# myirBoard.net
KiCad netlist of a schematic drawn in Altium Designer
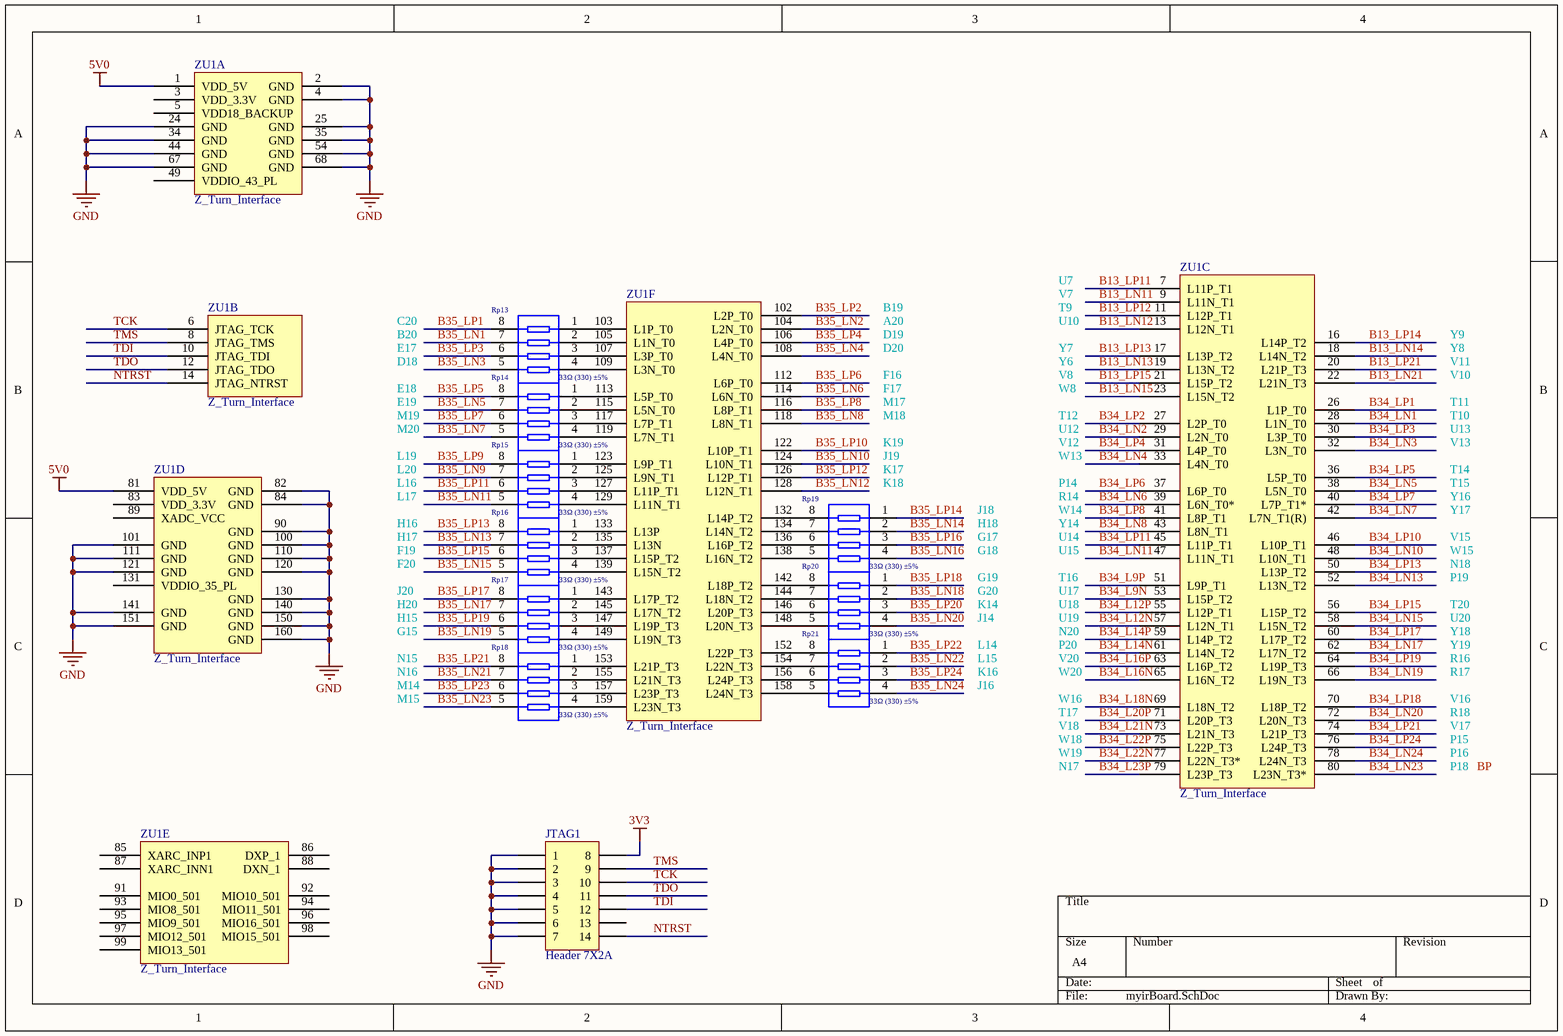
[diagram p0: myirBoard.SchDoc]

(export (version "E")
  (design (tool "Eeschema 10.0.6"))
  (components
    (comp (ref "JTAG1")
      (value "Header 7X2A")
      (footprint "HDR2X7_CEN")
      (description "Header, 7-Pin, Dual row")
      (fields (field (name "PUBLISHER") "Altium Limited"))
      (libsource (lib "Miscellaneous Connectors") (part "Header 7X2A"))
    )
    (comp (ref "Rp13")
      (value "33Ω (330) ±5%")
      (footprint "0402_Rx4")
      (description "贴片排阻")
      (libsource (lib "Miscellaneous Devices LC") (part "0402*4 33Ω (330) 5%"))
    )
    (comp (ref "Rp14")
      (value "33Ω (330) ±5%")
      (footprint "0402_Rx4")
      (description "贴片排阻")
      (libsource (lib "Miscellaneous Devices LC") (part "0402*4 33Ω (330) 5%"))
    )
    (comp (ref "Rp15")
      (value "33Ω (330) ±5%")
      (footprint "0402_Rx4")
      (description "贴片排阻")
      (libsource (lib "Miscellaneous Devices LC") (part "0402*4 33Ω (330) 5%"))
    )
    (comp (ref "Rp16")
      (value "33Ω (330) ±5%")
      (footprint "0402_Rx4")
      (description "贴片排阻")
      (libsource (lib "Miscellaneous Devices LC") (part "0402*4 33Ω (330) 5%"))
    )
    (comp (ref "Rp17")
      (value "33Ω (330) ±5%")
      (footprint "0402_Rx4")
      (description "贴片排阻")
      (libsource (lib "Miscellaneous Devices LC") (part "0402*4 33Ω (330) 5%"))
    )
    (comp (ref "Rp18")
      (value "33Ω (330) ±5%")
      (footprint "0402_Rx4")
      (description "贴片排阻")
      (libsource (lib "Miscellaneous Devices LC") (part "0402*4 33Ω (330) 5%"))
    )
    (comp (ref "Rp19")
      (value "33Ω (330) ±5%")
      (footprint "0402_Rx4")
      (description "贴片排阻")
      (libsource (lib "Miscellaneous Devices LC") (part "0402*4 33Ω (330) 5%"))
    )
    (comp (ref "Rp20")
      (value "33Ω (330) ±5%")
      (footprint "0402_Rx4")
      (description "贴片排阻")
      (libsource (lib "Miscellaneous Devices LC") (part "0402*4 33Ω (330) 5%"))
    )
    (comp (ref "Rp21")
      (value "33Ω (330) ±5%")
      (footprint "0402_Rx4")
      (description "贴片排阻")
      (libsource (lib "Miscellaneous Devices LC") (part "0402*4 33Ω (330) 5%"))
    )
    (comp (ref "ZU1")
      (value "Z_Turn_Interface")
      (footprint "ZTURN")
      (libsource (lib "zynqEXP_Schlib") (part "Z_Turn_Interface"))
    )
  )
  (nets
    (net (code "2") (name "/B13_LN11") (class "Default")
      (node (ref "ZU1") (pin "9") (pinfunction "L11N_T1_9") (pintype "passive"))
    )
    (net (code "3") (name "/B13_LN12") (class "Default")
      (node (ref "ZU1") (pin "13") (pinfunction "L12N_T1_13") (pintype "passive"))
    )
    (net (code "4") (name "/B13_LN13") (class "Default")
      (node (ref "ZU1") (pin "19") (pinfunction "L13N_T2_19") (pintype "passive"))
    )
    (net (code "5") (name "/B13_LN14") (class "Default")
      (node (ref "ZU1") (pin "18") (pinfunction "L14N_T2_18") (pintype "passive"))
    )
    (net (code "6") (name "/B13_LN15") (class "Default")
      (node (ref "ZU1") (pin "23") (pinfunction "L15N_T2_23") (pintype "passive"))
    )
    (net (code "7") (name "/B13_LN21") (class "Default")
      (node (ref "ZU1") (pin "22") (pinfunction "L21N_T3_22") (pintype "passive"))
    )
    (net (code "8") (name "/B13_LP11") (class "Default")
      (node (ref "ZU1") (pin "7") (pinfunction "L11P_T1_7") (pintype "passive"))
    )
    (net (code "9") (name "/B13_LP12") (class "Default")
      (node (ref "ZU1") (pin "11") (pinfunction "L12P_T1_11") (pintype "passive"))
    )
    (net (code "10") (name "/B13_LP13") (class "Default")
      (node (ref "ZU1") (pin "17") (pinfunction "L13P_T2_17") (pintype "passive"))
    )
    (net (code "11") (name "/B13_LP14") (class "Default")
      (node (ref "ZU1") (pin "16") (pinfunction "L14P_T2_16") (pintype "passive"))
    )
    (net (code "12") (name "/B13_LP15") (class "Default")
      (node (ref "ZU1") (pin "21") (pinfunction "L15P_T2_21") (pintype "passive"))
    )
    (net (code "13") (name "/B13_LP21") (class "Default")
      (node (ref "ZU1") (pin "20") (pinfunction "L21P_T3_20") (pintype "passive"))
    )
    (net (code "16") (name "/B34_L9N") (class "Default")
      (node (ref "ZU1") (pin "53") (pinfunction "L15P_T2_53") (pintype "passive"))
    )
    (net (code "17") (name "/B34_L9P") (class "Default")
      (node (ref "ZU1") (pin "51") (pinfunction "L9P_T1_51") (pintype "passive"))
    )
    (net (code "18") (name "/B34_L12N") (class "Default")
      (node (ref "ZU1") (pin "57") (pinfunction "L12N_T1_57") (pintype "passive"))
    )
    (net (code "19") (name "/B34_L12P") (class "Default")
      (node (ref "ZU1") (pin "55") (pinfunction "L12P_T1_55") (pintype "passive"))
    )
    (net (code "20") (name "/B34_L14N") (class "Default")
      (node (ref "ZU1") (pin "61") (pinfunction "L14N_T2_61") (pintype "passive"))
    )
    (net (code "21") (name "/B34_L14P") (class "Default")
      (node (ref "ZU1") (pin "59") (pinfunction "L14P_T2_59") (pintype "passive"))
    )
    (net (code "22") (name "/B34_L16N") (class "Default")
      (node (ref "ZU1") (pin "65") (pinfunction "L16N_T2_65") (pintype "passive"))
    )
    (net (code "23") (name "/B34_L16P") (class "Default")
      (node (ref "ZU1") (pin "63") (pinfunction "L16P_T2_63") (pintype "passive"))
    )
    (net (code "24") (name "/B34_L18N") (class "Default")
      (node (ref "ZU1") (pin "69") (pinfunction "L18N_T2_69") (pintype "passive"))
    )
    (net (code "25") (name "/B34_L20P") (class "Default")
      (node (ref "ZU1") (pin "71") (pinfunction "L20P_T3_71") (pintype "passive"))
    )
    (net (code "26") (name "/B34_L21N") (class "Default")
      (node (ref "ZU1") (pin "73") (pinfunction "L21N_T3_73") (pintype "passive"))
    )
    (net (code "27") (name "/B34_L22N") (class "Default")
      (node (ref "ZU1") (pin "77") (pinfunction "L22N_T3*_77") (pintype "passive"))
    )
    (net (code "28") (name "/B34_L22P") (class "Default")
      (node (ref "ZU1") (pin "75") (pinfunction "L22P_T3_75") (pintype "passive"))
    )
    (net (code "29") (name "/B34_L23P") (class "Default")
      (node (ref "ZU1") (pin "79") (pinfunction "L23P_T3_79") (pintype "passive"))
    )
    (net (code "30") (name "/B34_LN1") (class "Default")
      (node (ref "ZU1") (pin "28") (pinfunction "L1N_T0_28") (pintype "passive"))
    )
    (net (code "31") (name "/B34_LN2") (class "Default")
      (node (ref "ZU1") (pin "29") (pinfunction "L2N_T0_29") (pintype "passive"))
    )
    (net (code "32") (name "/B34_LN3") (class "Default")
      (node (ref "ZU1") (pin "32") (pinfunction "L3N_T0_32") (pintype "passive"))
    )
    (net (code "33") (name "/B34_LN4") (class "Default")
      (node (ref "ZU1") (pin "33") (pinfunction "L4N_T0_33") (pintype "passive"))
    )
    (net (code "34") (name "/B34_LN5") (class "Default")
      (node (ref "ZU1") (pin "38") (pinfunction "L5N_T0_38") (pintype "passive"))
    )
    (net (code "35") (name "/B34_LN6") (class "Default")
      (node (ref "ZU1") (pin "39") (pinfunction "L6N_T0*_39") (pintype "passive"))
    )
    (net (code "36") (name "/B34_LN7") (class "Default")
      (node (ref "ZU1") (pin "42") (pinfunction "L7N_T1(R)_42") (pintype "passive"))
    )
    (net (code "37") (name "/B34_LN8") (class "Default")
      (node (ref "ZU1") (pin "43") (pinfunction "L8N_T1_43") (pintype "passive"))
    )
    (net (code "38") (name "/B34_LN10") (class "Default")
      (node (ref "ZU1") (pin "48") (pinfunction "L10N_T1_48") (pintype "passive"))
    )
    (net (code "39") (name "/B34_LN11") (class "Default")
      (node (ref "ZU1") (pin "47") (pinfunction "L11N_T1_47") (pintype "passive"))
    )
    (net (code "40") (name "/B34_LN13") (class "Default")
      (node (ref "ZU1") (pin "52") (pinfunction "L13N_T2_52") (pintype "passive"))
    )
    (net (code "41") (name "/B34_LN15") (class "Default")
      (node (ref "ZU1") (pin "58") (pinfunction "L15N_T2_58") (pintype "passive"))
    )
    (net (code "42") (name "/B34_LN17") (class "Default")
      (node (ref "ZU1") (pin "62") (pinfunction "L17N_T2_62") (pintype "passive"))
    )
    (net (code "43") (name "/B34_LN19") (class "Default")
      (node (ref "ZU1") (pin "66") (pinfunction "L19N_T3_66") (pintype "passive"))
    )
    (net (code "44") (name "/B34_LN20") (class "Default")
      (node (ref "ZU1") (pin "72") (pinfunction "L20N_T3_72") (pintype "passive"))
    )
    (net (code "45") (name "/B34_LN23") (class "Default")
      (node (ref "ZU1") (pin "80") (pinfunction "L23N_T3*_80") (pintype "passive"))
    )
    (net (code "46") (name "/B34_LN24") (class "Default")
      (node (ref "ZU1") (pin "78") (pinfunction "L24N_T3_78") (pintype "passive"))
    )
    (net (code "47") (name "/B34_LP1") (class "Default")
      (node (ref "ZU1") (pin "26") (pinfunction "L1P_T0_26") (pintype "passive"))
    )
    (net (code "48") (name "/B34_LP2") (class "Default")
      (node (ref "ZU1") (pin "27") (pinfunction "L2P_T0_27") (pintype "passive"))
    )
    (net (code "49") (name "/B34_LP3") (class "Default")
      (node (ref "ZU1") (pin "30") (pinfunction "L3P_T0_30") (pintype "passive"))
    )
    (net (code "50") (name "/B34_LP4") (class "Default")
      (node (ref "ZU1") (pin "31") (pinfunction "L4P_T0_31") (pintype "passive"))
    )
    (net (code "51") (name "/B34_LP5") (class "Default")
      (node (ref "ZU1") (pin "36") (pinfunction "L5P_T0_36") (pintype "passive"))
    )
    (net (code "52") (name "/B34_LP6") (class "Default")
      (node (ref "ZU1") (pin "37") (pinfunction "L6P_T0_37") (pintype "passive"))
    )
    (net (code "53") (name "/B34_LP7") (class "Default")
      (node (ref "ZU1") (pin "40") (pinfunction "L7P_T1*_40") (pintype "passive"))
    )
    (net (code "54") (name "/B34_LP8") (class "Default")
      (node (ref "ZU1") (pin "41") (pinfunction "L8P_T1_41") (pintype "passive"))
    )
    (net (code "55") (name "/B34_LP10") (class "Default")
      (node (ref "ZU1") (pin "46") (pinfunction "L10P_T1_46") (pintype "passive"))
    )
    (net (code "56") (name "/B34_LP11") (class "Default")
      (node (ref "ZU1") (pin "45") (pinfunction "L11P_T1_45") (pintype "passive"))
    )
    (net (code "57") (name "/B34_LP13") (class "Default")
      (node (ref "ZU1") (pin "50") (pinfunction "L13P_T2_50") (pintype "passive"))
    )
    (net (code "58") (name "/B34_LP15") (class "Default")
      (node (ref "ZU1") (pin "56") (pinfunction "L15P_T2_56") (pintype "passive"))
    )
    (net (code "59") (name "/B34_LP17") (class "Default")
      (node (ref "ZU1") (pin "60") (pinfunction "L17P_T2_60") (pintype "passive"))
    )
    (net (code "60") (name "/B34_LP18") (class "Default")
      (node (ref "ZU1") (pin "70") (pinfunction "L18P_T2_70") (pintype "passive"))
    )
    (net (code "61") (name "/B34_LP19") (class "Default")
      (node (ref "ZU1") (pin "64") (pinfunction "L19P_T3_64") (pintype "passive"))
    )
    (net (code "62") (name "/B34_LP21") (class "Default")
      (node (ref "ZU1") (pin "74") (pinfunction "L21P_T3_74") (pintype "passive"))
    )
    (net (code "63") (name "/B34_LP24") (class "Default")
      (node (ref "ZU1") (pin "76") (pinfunction "L24P_T3_76") (pintype "passive"))
    )
    (net (code "64") (name "/B35_LN1") (class "Default")
      (node (ref "Rp13") (pin "7") (pinfunction "7_7") (pintype "passive"))
    )
    (net (code "65") (name "/B35_LN2") (class "Default")
      (node (ref "ZU1") (pin "104") (pinfunction "L2N_T0_104") (pintype "passive"))
    )
    (net (code "66") (name "/B35_LN3") (class "Default")
      (node (ref "Rp13") (pin "5") (pinfunction "5_5") (pintype "passive"))
    )
    (net (code "67") (name "/B35_LN4") (class "Default")
      (node (ref "ZU1") (pin "108") (pinfunction "L4N_T0_108") (pintype "passive"))
    )
    (net (code "68") (name "/B35_LN5") (class "Default")
      (node (ref "Rp14") (pin "7") (pinfunction "7_7") (pintype "passive"))
    )
    (net (code "69") (name "/B35_LN6") (class "Default")
      (node (ref "ZU1") (pin "114") (pinfunction "L6N_T0_114") (pintype "passive"))
    )
    (net (code "70") (name "/B35_LN7") (class "Default")
      (node (ref "Rp14") (pin "5") (pinfunction "5_5") (pintype "passive"))
    )
    (net (code "71") (name "/B35_LN8") (class "Default")
      (node (ref "ZU1") (pin "118") (pinfunction "L8N_T1_118") (pintype "passive"))
    )
    (net (code "72") (name "/B35_LN9") (class "Default")
      (node (ref "Rp15") (pin "7") (pinfunction "7_7") (pintype "passive"))
    )
    (net (code "73") (name "/B35_LN10") (class "Default")
      (node (ref "ZU1") (pin "124") (pinfunction "L10N_T1_124") (pintype "passive"))
    )
    (net (code "74") (name "/B35_LN11") (class "Default")
      (node (ref "Rp15") (pin "5") (pinfunction "5_5") (pintype "passive"))
    )
    (net (code "75") (name "/B35_LN12") (class "Default")
      (node (ref "ZU1") (pin "128") (pinfunction "L12N_T1_128") (pintype "passive"))
    )
    (net (code "76") (name "/B35_LN13") (class "Default")
      (node (ref "Rp16") (pin "7") (pinfunction "7_7") (pintype "passive"))
    )
    (net (code "77") (name "/B35_LN14") (class "Default")
      (node (ref "Rp19") (pin "2") (pinfunction "2_2") (pintype "passive"))
    )
    (net (code "78") (name "/B35_LN15") (class "Default")
      (node (ref "Rp16") (pin "5") (pinfunction "5_5") (pintype "passive"))
    )
    (net (code "79") (name "/B35_LN16") (class "Default")
      (node (ref "Rp19") (pin "4") (pinfunction "4_4") (pintype "passive"))
    )
    (net (code "80") (name "/B35_LN17") (class "Default")
      (node (ref "Rp17") (pin "7") (pinfunction "7_7") (pintype "passive"))
    )
    (net (code "81") (name "/B35_LN18") (class "Default")
      (node (ref "Rp20") (pin "2") (pinfunction "2_2") (pintype "passive"))
    )
    (net (code "82") (name "/B35_LN19") (class "Default")
      (node (ref "Rp17") (pin "5") (pinfunction "5_5") (pintype "passive"))
    )
    (net (code "83") (name "/B35_LN20") (class "Default")
      (node (ref "Rp20") (pin "4") (pinfunction "4_4") (pintype "passive"))
    )
    (net (code "84") (name "/B35_LN21") (class "Default")
      (node (ref "Rp18") (pin "7") (pinfunction "7_7") (pintype "passive"))
    )
    (net (code "85") (name "/B35_LN22") (class "Default")
      (node (ref "Rp21") (pin "2") (pinfunction "2_2") (pintype "passive"))
    )
    (net (code "86") (name "/B35_LN23") (class "Default")
      (node (ref "Rp18") (pin "5") (pinfunction "5_5") (pintype "passive"))
    )
    (net (code "87") (name "/B35_LN24") (class "Default")
      (node (ref "Rp21") (pin "4") (pinfunction "4_4") (pintype "passive"))
    )
    (net (code "88") (name "/B35_LP1") (class "Default")
      (node (ref "Rp13") (pin "8") (pinfunction "8_8") (pintype "passive"))
    )
    (net (code "89") (name "/B35_LP2") (class "Default")
      (node (ref "ZU1") (pin "102") (pinfunction "L2P_T0_102") (pintype "passive"))
    )
    (net (code "90") (name "/B35_LP3") (class "Default")
      (node (ref "Rp13") (pin "6") (pinfunction "6_6") (pintype "passive"))
    )
    (net (code "91") (name "/B35_LP4") (class "Default")
      (node (ref "ZU1") (pin "106") (pinfunction "L4P_T0_106") (pintype "passive"))
    )
    (net (code "92") (name "/B35_LP5") (class "Default")
      (node (ref "Rp14") (pin "8") (pinfunction "8_8") (pintype "passive"))
    )
    (net (code "93") (name "/B35_LP6") (class "Default")
      (node (ref "ZU1") (pin "112") (pinfunction "L6P_T0_112") (pintype "passive"))
    )
    (net (code "94") (name "/B35_LP7") (class "Default")
      (node (ref "Rp14") (pin "6") (pinfunction "6_6") (pintype "passive"))
    )
    (net (code "95") (name "/B35_LP8") (class "Default")
      (node (ref "ZU1") (pin "116") (pinfunction "L8P_T1_116") (pintype "passive"))
    )
    (net (code "96") (name "/B35_LP9") (class "Default")
      (node (ref "Rp15") (pin "8") (pinfunction "8_8") (pintype "passive"))
    )
    (net (code "97") (name "/B35_LP10") (class "Default")
      (node (ref "ZU1") (pin "122") (pinfunction "L10P_T1_122") (pintype "passive"))
    )
    (net (code "98") (name "/B35_LP11") (class "Default")
      (node (ref "Rp15") (pin "6") (pinfunction "6_6") (pintype "passive"))
    )
    (net (code "99") (name "/B35_LP12") (class "Default")
      (node (ref "ZU1") (pin "126") (pinfunction "L12P_T1_126") (pintype "passive"))
    )
    (net (code "100") (name "/B35_LP13") (class "Default")
      (node (ref "Rp16") (pin "8") (pinfunction "8_8") (pintype "passive"))
    )
    (net (code "101") (name "/B35_LP14") (class "Default")
      (node (ref "Rp19") (pin "1") (pinfunction "1_1") (pintype "passive"))
    )
    (net (code "102") (name "/B35_LP15") (class "Default")
      (node (ref "Rp16") (pin "6") (pinfunction "6_6") (pintype "passive"))
    )
    (net (code "103") (name "/B35_LP16") (class "Default")
      (node (ref "Rp19") (pin "3") (pinfunction "3_3") (pintype "passive"))
    )
    (net (code "104") (name "/B35_LP17") (class "Default")
      (node (ref "Rp17") (pin "8") (pinfunction "8_8") (pintype "passive"))
    )
    (net (code "105") (name "/B35_LP18") (class "Default")
      (node (ref "Rp20") (pin "1") (pinfunction "1_1") (pintype "passive"))
    )
    (net (code "106") (name "/B35_LP19") (class "Default")
      (node (ref "Rp17") (pin "6") (pinfunction "6_6") (pintype "passive"))
    )
    (net (code "107") (name "/B35_LP20") (class "Default")
      (node (ref "Rp20") (pin "3") (pinfunction "3_3") (pintype "passive"))
    )
    (net (code "108") (name "/B35_LP21") (class "Default")
      (node (ref "Rp18") (pin "8") (pinfunction "8_8") (pintype "passive"))
    )
    (net (code "109") (name "/B35_LP22") (class "Default")
      (node (ref "Rp21") (pin "1") (pinfunction "1_1") (pintype "passive"))
    )
    (net (code "110") (name "/B35_LP23") (class "Default")
      (node (ref "Rp18") (pin "6") (pinfunction "6_6") (pintype "passive"))
    )
    (net (code "111") (name "/B35_LP24") (class "Default")
      (node (ref "Rp21") (pin "3") (pinfunction "3_3") (pintype "passive"))
    )
    (net (code "161") (name "/NTRST") (class "Default")
      (node (ref "JTAG1") (pin "14") (pinfunction "14_14") (pintype "passive"))
      (node (ref "ZU1") (pin "14") (pinfunction "JTAG_NTRST_14") (pintype "passive"))
    )
    (net (code "181") (name "/TCK") (class "Default")
      (node (ref "JTAG1") (pin "10") (pinfunction "10_10") (pintype "passive"))
      (node (ref "ZU1") (pin "6") (pinfunction "JTAG_TCK_6") (pintype "passive"))
    )
    (net (code "182") (name "/TDI") (class "Default")
      (node (ref "JTAG1") (pin "12") (pinfunction "12_12") (pintype "passive"))
      (node (ref "ZU1") (pin "10") (pinfunction "JTAG_TDI_10") (pintype "passive"))
    )
    (net (code "183") (name "/TDO") (class "Default")
      (node (ref "JTAG1") (pin "11") (pinfunction "11_11") (pintype "passive"))
      (node (ref "ZU1") (pin "12") (pinfunction "JTAG_TDO_12") (pintype "passive"))
    )
    (net (code "184") (name "/TMS") (class "Default")
      (node (ref "JTAG1") (pin "9") (pinfunction "9_9") (pintype "passive"))
      (node (ref "ZU1") (pin "8") (pinfunction "JTAG_TMS_8") (pintype "passive"))
    )
    (net (code "223") (name "3V3") (class "Default")
      (node (ref "JTAG1") (pin "8") (pinfunction "8_8") (pintype "passive"))
    )
    (net (code "224") (name "5V0") (class "Default")
      (node (ref "ZU1") (pin "1") (pinfunction "VDD_5V_1") (pintype "passive"))
      (node (ref "ZU1") (pin "81") (pinfunction "VDD_5V_81") (pintype "passive"))
    )
    (net (code "225") (name "GND") (class "Default")
      (node (ref "JTAG1") (pin "1") (pinfunction "1_1") (pintype "passive"))
      (node (ref "JTAG1") (pin "2") (pinfunction "2_2") (pintype "passive"))
      (node (ref "JTAG1") (pin "3") (pinfunction "3_3") (pintype "passive"))
      (node (ref "JTAG1") (pin "4") (pinfunction "4_4") (pintype "passive"))
      (node (ref "JTAG1") (pin "5") (pinfunction "5_5") (pintype "passive"))
      (node (ref "JTAG1") (pin "6") (pinfunction "6_6") (pintype "passive"))
      (node (ref "JTAG1") (pin "7") (pinfunction "7_7") (pintype "passive"))
      (node (ref "ZU1") (pin "100") (pinfunction "GND_100") (pintype "passive"))
      (node (ref "ZU1") (pin "101") (pinfunction "GND_101") (pintype "passive"))
      (node (ref "ZU1") (pin "110") (pinfunction "GND_110") (pintype "passive"))
      (node (ref "ZU1") (pin "111") (pinfunction "GND_111") (pintype "passive"))
      (node (ref "ZU1") (pin "120") (pinfunction "GND_120") (pintype "passive"))
      (node (ref "ZU1") (pin "121") (pinfunction "GND_121") (pintype "passive"))
      (node (ref "ZU1") (pin "130") (pinfunction "GND_130") (pintype "passive"))
      (node (ref "ZU1") (pin "140") (pinfunction "GND_140") (pintype "passive"))
      (node (ref "ZU1") (pin "141") (pinfunction "GND_141") (pintype "passive"))
      (node (ref "ZU1") (pin "150") (pinfunction "GND_150") (pintype "passive"))
      (node (ref "ZU1") (pin "151") (pinfunction "GND_151") (pintype "passive"))
      (node (ref "ZU1") (pin "160") (pinfunction "GND_160") (pintype "passive"))
      (node (ref "ZU1") (pin "2") (pinfunction "GND_2") (pintype "passive"))
      (node (ref "ZU1") (pin "24") (pinfunction "GND_24") (pintype "passive"))
      (node (ref "ZU1") (pin "25") (pinfunction "GND_25") (pintype "passive"))
      (node (ref "ZU1") (pin "34") (pinfunction "GND_34") (pintype "passive"))
      (node (ref "ZU1") (pin "35") (pinfunction "GND_35") (pintype "passive"))
      (node (ref "ZU1") (pin "4") (pinfunction "GND_4") (pintype "passive"))
      (node (ref "ZU1") (pin "44") (pinfunction "GND_44") (pintype "passive"))
      (node (ref "ZU1") (pin "54") (pinfunction "GND_54") (pintype "passive"))
      (node (ref "ZU1") (pin "67") (pinfunction "GND_67") (pintype "passive"))
      (node (ref "ZU1") (pin "68") (pinfunction "GND_68") (pintype "passive"))
      (node (ref "ZU1") (pin "82") (pinfunction "GND_82") (pintype "passive"))
      (node (ref "ZU1") (pin "84") (pinfunction "GND_84") (pintype "passive"))
      (node (ref "ZU1") (pin "90") (pinfunction "GND_90") (pintype "passive"))
    )
    (net (code "226") (name "Net-(ZU1F-L1N_T0)") (class "Default")
      (node (ref "Rp13") (pin "2") (pinfunction "2_2") (pintype "passive"))
      (node (ref "ZU1") (pin "105") (pinfunction "L1N_T0_105") (pintype "passive"))
    )
    (net (code "227") (name "Net-(ZU1F-L1P_T0)") (class "Default")
      (node (ref "Rp13") (pin "1") (pinfunction "1_1") (pintype "passive"))
      (node (ref "ZU1") (pin "103") (pinfunction "L1P_T0_103") (pintype "passive"))
    )
    (net (code "228") (name "Net-(ZU1F-L3N_T0)") (class "Default")
      (node (ref "Rp13") (pin "4") (pinfunction "4_4") (pintype "passive"))
      (node (ref "ZU1") (pin "109") (pinfunction "L3N_T0_109") (pintype "passive"))
    )
    (net (code "229") (name "Net-(ZU1F-L3P_T0)") (class "Default")
      (node (ref "Rp13") (pin "3") (pinfunction "3_3") (pintype "passive"))
      (node (ref "ZU1") (pin "107") (pinfunction "L3P_T0_107") (pintype "passive"))
    )
    (net (code "230") (name "Net-(ZU1F-L5N_T0)") (class "Default")
      (node (ref "Rp14") (pin "2") (pinfunction "2_2") (pintype "passive"))
      (node (ref "ZU1") (pin "115") (pinfunction "L5N_T0_115") (pintype "passive"))
    )
    (net (code "231") (name "Net-(ZU1F-L5P_T0)") (class "Default")
      (node (ref "Rp14") (pin "1") (pinfunction "1_1") (pintype "passive"))
      (node (ref "ZU1") (pin "113") (pinfunction "L5P_T0_113") (pintype "passive"))
    )
    (net (code "232") (name "Net-(ZU1F-L7N_T1)") (class "Default")
      (node (ref "Rp14") (pin "4") (pinfunction "4_4") (pintype "passive"))
      (node (ref "ZU1") (pin "119") (pinfunction "L7N_T1_119") (pintype "passive"))
    )
    (net (code "233") (name "Net-(ZU1F-L7P_T1)") (class "Default")
      (node (ref "Rp14") (pin "3") (pinfunction "3_3") (pintype "passive"))
      (node (ref "ZU1") (pin "117") (pinfunction "L7P_T1_117") (pintype "passive"))
    )
    (net (code "234") (name "Net-(ZU1F-L9N_T1)") (class "Default")
      (node (ref "Rp15") (pin "2") (pinfunction "2_2") (pintype "passive"))
      (node (ref "ZU1") (pin "125") (pinfunction "L9N_T1_125") (pintype "passive"))
    )
    (net (code "235") (name "Net-(ZU1F-L9P_T1)") (class "Default")
      (node (ref "Rp15") (pin "1") (pinfunction "1_1") (pintype "passive"))
      (node (ref "ZU1") (pin "123") (pinfunction "L9P_T1_123") (pintype "passive"))
    )
    (net (code "236") (name "Net-(ZU1F-L11N_T1)") (class "Default")
      (node (ref "Rp15") (pin "4") (pinfunction "4_4") (pintype "passive"))
      (node (ref "ZU1") (pin "129") (pinfunction "L11N_T1_129") (pintype "passive"))
    )
    (net (code "237") (name "Net-(ZU1F-L11P_T1)") (class "Default")
      (node (ref "Rp15") (pin "3") (pinfunction "3_3") (pintype "passive"))
      (node (ref "ZU1") (pin "127") (pinfunction "L11P_T1_127") (pintype "passive"))
    )
    (net (code "238") (name "Net-(ZU1F-L13N)") (class "Default")
      (node (ref "Rp16") (pin "2") (pinfunction "2_2") (pintype "passive"))
      (node (ref "ZU1") (pin "135") (pinfunction "L13N_135") (pintype "passive"))
    )
    (net (code "239") (name "Net-(ZU1F-L13P)") (class "Default")
      (node (ref "Rp16") (pin "1") (pinfunction "1_1") (pintype "passive"))
      (node (ref "ZU1") (pin "133") (pinfunction "L13P_133") (pintype "passive"))
    )
    (net (code "240") (name "Net-(ZU1F-L14N_T2)") (class "Default")
      (node (ref "Rp19") (pin "7") (pinfunction "7_7") (pintype "passive"))
      (node (ref "ZU1") (pin "134") (pinfunction "L14N_T2_134") (pintype "passive"))
    )
    (net (code "241") (name "Net-(ZU1F-L14P_T2)") (class "Default")
      (node (ref "Rp19") (pin "8") (pinfunction "8_8") (pintype "passive"))
      (node (ref "ZU1") (pin "132") (pinfunction "L14P_T2_132") (pintype "passive"))
    )
    (net (code "242") (name "Net-(ZU1F-L15N_T2)") (class "Default")
      (node (ref "Rp16") (pin "4") (pinfunction "4_4") (pintype "passive"))
      (node (ref "ZU1") (pin "139") (pinfunction "L15N_T2_139") (pintype "passive"))
    )
    (net (code "243") (name "Net-(ZU1F-L15P_T2)") (class "Default")
      (node (ref "Rp16") (pin "3") (pinfunction "3_3") (pintype "passive"))
      (node (ref "ZU1") (pin "137") (pinfunction "L15P_T2_137") (pintype "passive"))
    )
    (net (code "244") (name "Net-(ZU1F-L16N_T2)") (class "Default")
      (node (ref "Rp19") (pin "5") (pinfunction "5_5") (pintype "passive"))
      (node (ref "ZU1") (pin "138") (pinfunction "L16N_T2_138") (pintype "passive"))
    )
    (net (code "245") (name "Net-(ZU1F-L16P_T2)") (class "Default")
      (node (ref "Rp19") (pin "6") (pinfunction "6_6") (pintype "passive"))
      (node (ref "ZU1") (pin "136") (pinfunction "L16P_T2_136") (pintype "passive"))
    )
    (net (code "246") (name "Net-(ZU1F-L17N_T2)") (class "Default")
      (node (ref "Rp17") (pin "2") (pinfunction "2_2") (pintype "passive"))
      (node (ref "ZU1") (pin "145") (pinfunction "L17N_T2_145") (pintype "passive"))
    )
    (net (code "247") (name "Net-(ZU1F-L17P_T2)") (class "Default")
      (node (ref "Rp17") (pin "1") (pinfunction "1_1") (pintype "passive"))
      (node (ref "ZU1") (pin "143") (pinfunction "L17P_T2_143") (pintype "passive"))
    )
    (net (code "248") (name "Net-(ZU1F-L18N_T2)") (class "Default")
      (node (ref "Rp20") (pin "7") (pinfunction "7_7") (pintype "passive"))
      (node (ref "ZU1") (pin "144") (pinfunction "L18N_T2_144") (pintype "passive"))
    )
    (net (code "249") (name "Net-(ZU1F-L18P_T2)") (class "Default")
      (node (ref "Rp20") (pin "8") (pinfunction "8_8") (pintype "passive"))
      (node (ref "ZU1") (pin "142") (pinfunction "L18P_T2_142") (pintype "passive"))
    )
    (net (code "250") (name "Net-(ZU1F-L19N_T3)") (class "Default")
      (node (ref "Rp17") (pin "4") (pinfunction "4_4") (pintype "passive"))
      (node (ref "ZU1") (pin "149") (pinfunction "L19N_T3_149") (pintype "passive"))
    )
    (net (code "251") (name "Net-(ZU1F-L19P_T3)") (class "Default")
      (node (ref "Rp17") (pin "3") (pinfunction "3_3") (pintype "passive"))
      (node (ref "ZU1") (pin "147") (pinfunction "L19P_T3_147") (pintype "passive"))
    )
    (net (code "252") (name "Net-(ZU1F-L20N_T3)") (class "Default")
      (node (ref "Rp20") (pin "5") (pinfunction "5_5") (pintype "passive"))
      (node (ref "ZU1") (pin "148") (pinfunction "L20N_T3_148") (pintype "passive"))
    )
    (net (code "253") (name "Net-(ZU1F-L20P_T3)") (class "Default")
      (node (ref "Rp20") (pin "6") (pinfunction "6_6") (pintype "passive"))
      (node (ref "ZU1") (pin "146") (pinfunction "L20P_T3_146") (pintype "passive"))
    )
    (net (code "254") (name "Net-(ZU1F-L21N_T3)") (class "Default")
      (node (ref "Rp18") (pin "2") (pinfunction "2_2") (pintype "passive"))
      (node (ref "ZU1") (pin "155") (pinfunction "L21N_T3_155") (pintype "passive"))
    )
    (net (code "255") (name "Net-(ZU1F-L21P_T3)") (class "Default")
      (node (ref "Rp18") (pin "1") (pinfunction "1_1") (pintype "passive"))
      (node (ref "ZU1") (pin "153") (pinfunction "L21P_T3_153") (pintype "passive"))
    )
    (net (code "256") (name "Net-(ZU1F-L22N_T3)") (class "Default")
      (node (ref "Rp21") (pin "7") (pinfunction "7_7") (pintype "passive"))
      (node (ref "ZU1") (pin "154") (pinfunction "L22N_T3_154") (pintype "passive"))
    )
    (net (code "257") (name "Net-(ZU1F-L22P_T3)") (class "Default")
      (node (ref "Rp21") (pin "8") (pinfunction "8_8") (pintype "passive"))
      (node (ref "ZU1") (pin "152") (pinfunction "L22P_T3_152") (pintype "passive"))
    )
    (net (code "258") (name "Net-(ZU1F-L23N_T3)") (class "Default")
      (node (ref "Rp18") (pin "4") (pinfunction "4_4") (pintype "passive"))
      (node (ref "ZU1") (pin "159") (pinfunction "L23N_T3_159") (pintype "passive"))
    )
    (net (code "259") (name "Net-(ZU1F-L23P_T3)") (class "Default")
      (node (ref "Rp18") (pin "3") (pinfunction "3_3") (pintype "passive"))
      (node (ref "ZU1") (pin "157") (pinfunction "L23P_T3_157") (pintype "passive"))
    )
    (net (code "260") (name "Net-(ZU1F-L24N_T3)") (class "Default")
      (node (ref "Rp21") (pin "5") (pinfunction "5_5") (pintype "passive"))
      (node (ref "ZU1") (pin "158") (pinfunction "L24N_T3_158") (pintype "passive"))
    )
    (net (code "261") (name "Net-(ZU1F-L24P_T3)") (class "Default")
      (node (ref "Rp21") (pin "6") (pinfunction "6_6") (pintype "passive"))
      (node (ref "ZU1") (pin "156") (pinfunction "L24P_T3_156") (pintype "passive"))
    )
    (net (code "262") (name "unconnected-(JTAG1-Pad13)") (class "Default")
      (node (ref "JTAG1") (pin "13") (pinfunction "13_13") (pintype "passive"))
    )
    (net (code "263") (name "unconnected-(ZU1A-VDD18_BACKUP-Pad5)") (class "Default")
      (node (ref "ZU1") (pin "5") (pinfunction "VDD18_BACKUP_5") (pintype "passive"))
    )
    (net (code "264") (name "unconnected-(ZU1A-VDDIO_43_PL-Pad49)") (class "Default")
      (node (ref "ZU1") (pin "49") (pinfunction "VDDIO_43_PL_49") (pintype "passive"))
    )
    (net (code "265") (name "unconnected-(ZU1A-VDD_3.3V-Pad3)") (class "Default")
      (node (ref "ZU1") (pin "3") (pinfunction "VDD_3.3V_3") (pintype "passive"))
    )
    (net (code "266") (name "unconnected-(ZU1D-VDDIO_35_PL-Pad131)") (class "Default")
      (node (ref "ZU1") (pin "131") (pinfunction "VDDIO_35_PL_131") (pintype "passive"))
    )
    (net (code "267") (name "unconnected-(ZU1D-VDD_3.3V-Pad83)") (class "Default")
      (node (ref "ZU1") (pin "83") (pinfunction "VDD_3.3V_83") (pintype "passive"))
    )
    (net (code "268") (name "unconnected-(ZU1D-XADC_VCC-Pad89)") (class "Default")
      (node (ref "ZU1") (pin "89") (pinfunction "XADC_VCC_89") (pintype "passive"))
    )
    (net (code "269") (name "unconnected-(ZU1E-DXN_1-Pad88)") (class "Default")
      (node (ref "ZU1") (pin "88") (pinfunction "DXN_1_88") (pintype "passive"))
    )
    (net (code "270") (name "unconnected-(ZU1E-DXP_1-Pad86)") (class "Default")
      (node (ref "ZU1") (pin "86") (pinfunction "DXP_1_86") (pintype "passive"))
    )
    (net (code "271") (name "unconnected-(ZU1E-MIO0_501-Pad91)") (class "Default")
      (node (ref "ZU1") (pin "91") (pinfunction "MIO0_501_91") (pintype "passive"))
    )
    (net (code "272") (name "unconnected-(ZU1E-MIO8_501-Pad93)") (class "Default")
      (node (ref "ZU1") (pin "93") (pinfunction "MIO8_501_93") (pintype "passive"))
    )
    (net (code "273") (name "unconnected-(ZU1E-MIO9_501-Pad95)") (class "Default")
      (node (ref "ZU1") (pin "95") (pinfunction "MIO9_501_95") (pintype "passive"))
    )
    (net (code "274") (name "unconnected-(ZU1E-MIO10_501-Pad92)") (class "Default")
      (node (ref "ZU1") (pin "92") (pinfunction "MIO10_501_92") (pintype "passive"))
    )
    (net (code "275") (name "unconnected-(ZU1E-MIO11_501-Pad94)") (class "Default")
      (node (ref "ZU1") (pin "94") (pinfunction "MIO11_501_94") (pintype "passive"))
    )
    (net (code "276") (name "unconnected-(ZU1E-MIO12_501-Pad97)") (class "Default")
      (node (ref "ZU1") (pin "97") (pinfunction "MIO12_501_97") (pintype "passive"))
    )
    (net (code "277") (name "unconnected-(ZU1E-MIO13_501-Pad99)") (class "Default")
      (node (ref "ZU1") (pin "99") (pinfunction "MIO13_501_99") (pintype "passive"))
    )
    (net (code "278") (name "unconnected-(ZU1E-MIO15_501-Pad98)") (class "Default")
      (node (ref "ZU1") (pin "98") (pinfunction "MIO15_501_98") (pintype "passive"))
    )
    (net (code "279") (name "unconnected-(ZU1E-MIO16_501-Pad96)") (class "Default")
      (node (ref "ZU1") (pin "96") (pinfunction "MIO16_501_96") (pintype "passive"))
    )
    (net (code "280") (name "unconnected-(ZU1E-XARC_INN1-Pad87)") (class "Default")
      (node (ref "ZU1") (pin "87") (pinfunction "XARC_INN1_87") (pintype "passive"))
    )
    (net (code "281") (name "unconnected-(ZU1E-XARC_INP1-Pad85)") (class "Default")
      (node (ref "ZU1") (pin "85") (pinfunction "XARC_INP1_85") (pintype "passive"))
    )
  )
)
